# project1.net
KiCad netlist of a schematic drawn in Altium Designer
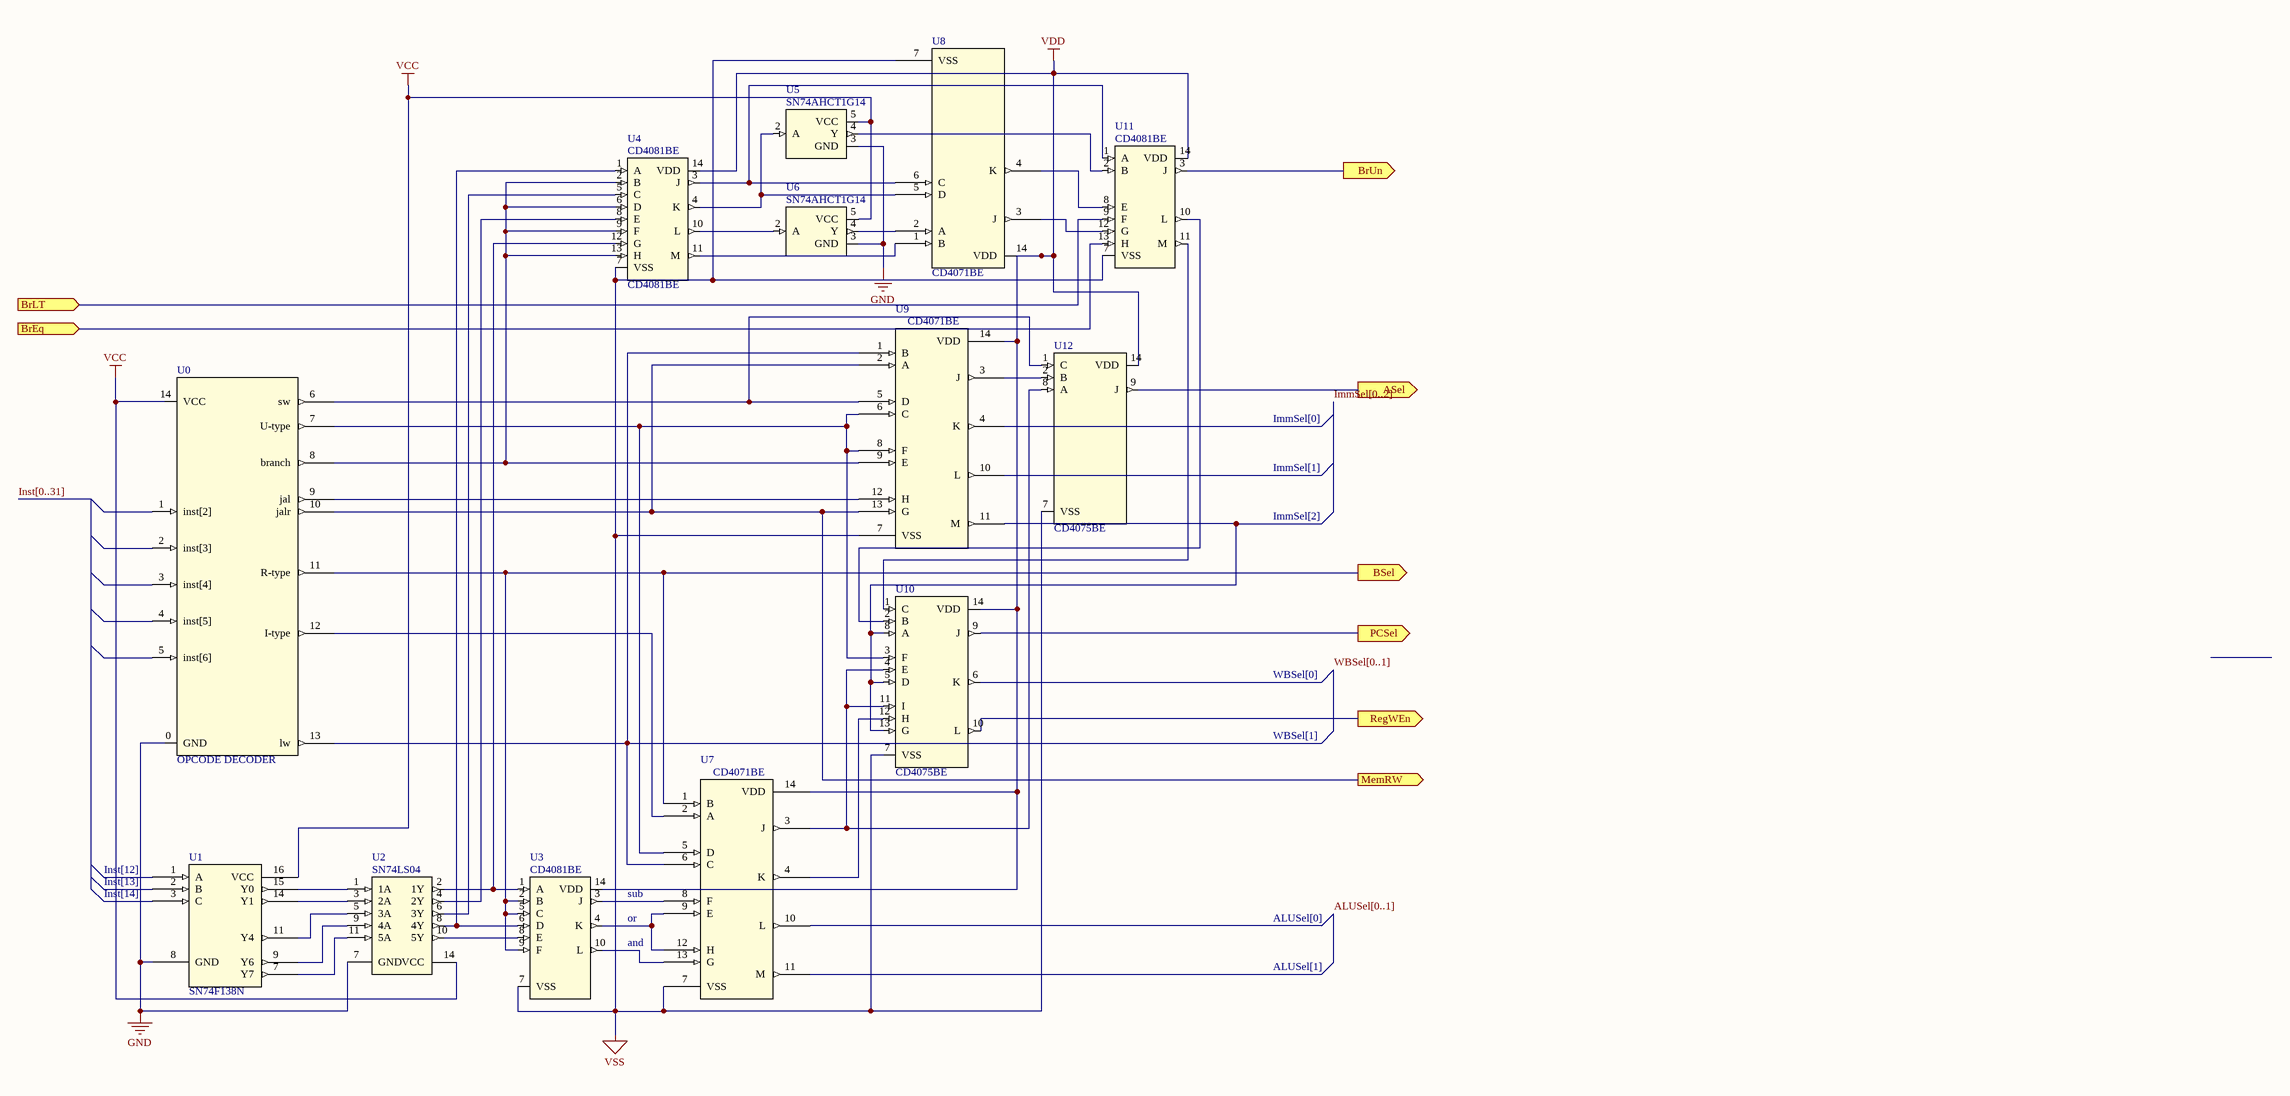
[diagram p0: project1.SchDoc]

(export (version "E")
  (design (tool "Eeschema 10.0.6"))
  (components
    (comp (ref "U0") (value "OPCODE DECODER") (libsource (lib "Project1") (part "OPCODE DECODER FS")))
    (comp (ref "U1")
      (value "SN74F138N")
      (footprint "N16")
      (description "No Description Available")
      (fields (field (name "COPYRIGHT") "Copyright (C) 2023 Ultra Librarian. All rights reserved."))
      (libsource (lib "SN74F138N") (part "SN74F138N_1"))
    )
    (comp (ref "U2")
      (value "SN74LS04N")
      (footprint "N14")
      (description "No Description Available")
      (fields (field (name "COPYRIGHT") "Copyright (C) 2023 Ultra Librarian. All rights reserved."))
      (libsource (lib "SN74LS04N") (part "SN74LS04N"))
    )
    (comp (ref "U3")
      (value "CD4081BE")
      (footprint "N14")
      (description "No Description Available")
      (fields (field (name "COPYRIGHT") "Copyright (C) 2023 Ultra Librarian. All rights reserved."))
      (libsource (lib "CD4081BE") (part "CD4081BE"))
    )
    (comp (ref "U4")
      (value "CD4081BE")
      (footprint "N14")
      (description "No Description Available")
      (fields (field (name "COPYRIGHT") "Copyright (C) 2023 Ultra Librarian. All rights reserved."))
      (libsource (lib "CD4081BE") (part "CD4081BE"))
    )
    (comp (ref "U5")
      (value "CAHCT1G14QDCKRQ1")
      (footprint "DCK5_TEX")
      (description "No Description Available")
      (fields (field (name "COPYRIGHT") "Copyright (C) 2023 Ultra Librarian. All rights reserved."))
      (libsource (lib "CAHCT1G14QDCKRQ1") (part "CAHCT1G14QDCKRQ1"))
    )
    (comp (ref "U6")
      (value "AHCT1G14QDCKRQ1")
      (footprint "DCK5_TEX")
      (description "No Description Available")
      (fields
        (field (name "MANUFACTURER_PART_NUMBER") "CAHCT1G14QDCKRQ1")
        (field (name "COPYRIGHT") "Copyright (C) 2023 Ultra Librarian. All rights reserved.")
      )
      (libsource (lib "CAHCT1G14QDCKRQ1") (part "CAHCT1G14QDCKRQ1"))
    )
    (comp (ref "U7")
      (value "CD4071BE")
      (footprint "N14")
      (description "No Description Available")
      (fields (field (name "COPYRIGHT") "Copyright (C) 2023 Ultra Librarian. All rights reserved."))
      (libsource (lib "") (part "CD4071BE_1"))
    )
    (comp (ref "U8")
      (value "CD4071BE")
      (footprint "N14")
      (description "No Description Available")
      (fields (field (name "COPYRIGHT") "Copyright (C) 2023 Ultra Librarian. All rights reserved."))
      (libsource (lib "CD4071BE") (part "CD4071BE"))
    )
    (comp (ref "U9")
      (value "CD4071BE")
      (footprint "N14")
      (description "No Description Available")
      (fields (field (name "COPYRIGHT") "Copyright (C) 2023 Ultra Librarian. All rights reserved."))
      (libsource (lib "") (part "CD4071BE_1"))
    )
    (comp (ref "U10")
      (value "CD4075BE")
      (footprint "N14")
      (description "No Description Available")
      (fields (field (name "COPYRIGHT") "Copyright (C) 2023 Ultra Librarian. All rights reserved."))
      (libsource (lib "CD4075BE") (part "CD4075BE"))
    )
    (comp (ref "U11")
      (value "CD4081BE")
      (footprint "N14")
      (description "No Description Available")
      (fields (field (name "COPYRIGHT") "Copyright (C) 2023 Ultra Librarian. All rights reserved."))
      (libsource (lib "CD4081BE") (part "CD4081BE"))
    )
    (comp (ref "U12")
      (value "CD4075BE")
      (footprint "N14")
      (description "No Description Available")
      (fields (field (name "COPYRIGHT") "Copyright (C) 2023 Ultra Librarian. All rights reserved."))
      (libsource (lib "CD4075BE") (part "CD4075BE"))
    )
  )
  (nets
    (net (code "41") (name "/ASel") (class "Default")
      (node (ref "U12") (pin "9") (pinfunction "J_9") (pintype "output"))
    )
    (net (code "42") (name "/BSel") (class "Default")
      (node (ref "U0") (pin "11") (pinfunction "R-type_11") (pintype "output"))
      (node (ref "U3") (pin "2") (pinfunction "B_2") (pintype "input"))
      (node (ref "U3") (pin "5") (pinfunction "C_5") (pintype "input"))
      (node (ref "U3") (pin "9") (pinfunction "F_9") (pintype "input"))
      (node (ref "U7") (pin "1") (pinfunction "B_1") (pintype "input"))
    )
    (net (code "43") (name "/BrEq") (class "Default")
      (node (ref "U11") (pin "13") (pinfunction "H_13") (pintype "input"))
    )
    (net (code "44") (name "/BrLT") (class "Default")
      (node (ref "U11") (pin "9") (pinfunction "F_9") (pintype "input"))
    )
    (net (code "45") (name "/BrUn") (class "Default")
      (node (ref "U11") (pin "3") (pinfunction "J_3") (pintype "output"))
    )
    (net (code "48") (name "/MemRW") (class "Default")
      (node (ref "U0") (pin "10") (pinfunction "jalr_10") (pintype "output"))
      (node (ref "U9") (pin "13") (pinfunction "G_13") (pintype "input"))
      (node (ref "U9") (pin "2") (pinfunction "A_2") (pintype "input"))
    )
    (net (code "49") (name "/PCSel") (class "Default")
      (node (ref "U10") (pin "9") (pinfunction "J_9") (pintype "output"))
    )
    (net (code "50") (name "/RegWEn") (class "Default")
      (node (ref "U10") (pin "10") (pinfunction "L_10") (pintype "output"))
    )
    (net (code "52") (name "GND") (class "Default")
      (node (ref "U0") (pin "0") (pinfunction "GND_0") (pintype "power_in"))
      (node (ref "U1") (pin "8") (pinfunction "GND_8") (pintype "power_in"))
      (node (ref "U2") (pin "7") (pinfunction "GND_7") (pintype "power_in"))
      (node (ref "U5") (pin "3") (pinfunction "GND_3") (pintype "power_in"))
      (node (ref "U6") (pin "3") (pinfunction "GND_3") (pintype "power_in"))
    )
    (net (code "53") (name "Net-(U0-I-type)") (class "Default")
      (node (ref "U0") (pin "12") (pinfunction "I-type_12") (pintype "output"))
      (node (ref "U7") (pin "2") (pinfunction "A_2") (pintype "input"))
    )
    (net (code "54") (name "Net-(U0-U-type)") (class "Default")
      (node (ref "U0") (pin "7") (pinfunction "U-type_7") (pintype "output"))
      (node (ref "U10") (pin "3") (pinfunction "F_3") (pintype "input"))
      (node (ref "U7") (pin "5") (pinfunction "D_5") (pintype "input"))
      (node (ref "U9") (pin "6") (pinfunction "C_6") (pintype "input"))
      (node (ref "U9") (pin "8") (pinfunction "F_8") (pintype "input"))
    )
    (net (code "55") (name "Net-(U0-branch)") (class "Default")
      (node (ref "U0") (pin "8") (pinfunction "branch_8") (pintype "output"))
      (node (ref "U4") (pin "13") (pinfunction "H_13") (pintype "input"))
      (node (ref "U4") (pin "2") (pinfunction "B_2") (pintype "input"))
      (node (ref "U4") (pin "6") (pinfunction "D_6") (pintype "input"))
      (node (ref "U4") (pin "9") (pinfunction "F_9") (pintype "input"))
      (node (ref "U9") (pin "9") (pinfunction "E_9") (pintype "input"))
    )
    (net (code "56") (name "Net-(U0-jal)") (class "Default")
      (node (ref "U0") (pin "9") (pinfunction "jal_9") (pintype "output"))
      (node (ref "U9") (pin "12") (pinfunction "H_12") (pintype "input"))
    )
    (net (code "57") (name "Net-(U0-lw)") (class "Default")
      (node (ref "U0") (pin "13") (pinfunction "lw_13") (pintype "output"))
      (node (ref "U7") (pin "6") (pinfunction "C_6") (pintype "input"))
      (node (ref "U9") (pin "1") (pinfunction "B_1") (pintype "input"))
    )
    (net (code "58") (name "Net-(U0-sw)") (class "Default")
      (node (ref "U0") (pin "6") (pinfunction "sw_6") (pintype "output"))
      (node (ref "U12") (pin "1") (pinfunction "C_1") (pintype "input"))
      (node (ref "U9") (pin "5") (pinfunction "D_5") (pintype "input"))
    )
    (net (code "59") (name "Net-(U1-Y0)") (class "Default")
      (node (ref "U1") (pin "15") (pinfunction "Y0_15") (pintype "output"))
      (node (ref "U2") (pin "1") (pinfunction "1A_1") (pintype "input"))
    )
    (net (code "60") (name "Net-(U1-Y1)") (class "Default")
      (node (ref "U1") (pin "14") (pinfunction "Y1_14") (pintype "output"))
      (node (ref "U2") (pin "3") (pinfunction "2A_3") (pintype "input"))
    )
    (net (code "61") (name "Net-(U1-Y4)") (class "Default")
      (node (ref "U1") (pin "11") (pinfunction "Y4_11") (pintype "output"))
      (node (ref "U2") (pin "5") (pinfunction "3A_5") (pintype "input"))
    )
    (net (code "62") (name "Net-(U1-Y6)") (class "Default")
      (node (ref "U1") (pin "9") (pinfunction "Y6_9") (pintype "output"))
      (node (ref "U2") (pin "9") (pinfunction "4A_9") (pintype "input"))
    )
    (net (code "63") (name "Net-(U1-Y7)") (class "Default")
      (node (ref "U1") (pin "7") (pinfunction "Y7_7") (pintype "output"))
      (node (ref "U2") (pin "11") (pinfunction "5A_11") (pintype "input"))
    )
    (net (code "64") (name "Net-(U2-1Y)") (class "Default")
      (node (ref "U2") (pin "2") (pinfunction "1Y_2") (pintype "output"))
      (node (ref "U3") (pin "1") (pinfunction "A_1") (pintype "input"))
      (node (ref "U4") (pin "12") (pinfunction "G_12") (pintype "input"))
    )
    (net (code "65") (name "Net-(U2-2Y)") (class "Default")
      (node (ref "U2") (pin "4") (pinfunction "2Y_4") (pintype "output"))
      (node (ref "U4") (pin "8") (pinfunction "E_8") (pintype "input"))
    )
    (net (code "66") (name "Net-(U2-3Y)") (class "Default")
      (node (ref "U2") (pin "6") (pinfunction "3Y_6") (pintype "output"))
      (node (ref "U4") (pin "5") (pinfunction "C_5") (pintype "input"))
    )
    (net (code "67") (name "Net-(U2-4Y)") (class "Default")
      (node (ref "U2") (pin "8") (pinfunction "4Y_8") (pintype "output"))
      (node (ref "U3") (pin "6") (pinfunction "D_6") (pintype "input"))
      (node (ref "U4") (pin "1") (pinfunction "A_1") (pintype "input"))
    )
    (net (code "68") (name "Net-(U2-5Y)") (class "Default")
      (node (ref "U2") (pin "10") (pinfunction "5Y_10") (pintype "output"))
      (node (ref "U3") (pin "8") (pinfunction "E_8") (pintype "input"))
    )
    (net (code "69") (name "Net-(U3-J)") (class "Default")
      (node (ref "U3") (pin "3") (pinfunction "J_3") (pintype "output"))
      (node (ref "U7") (pin "8") (pinfunction "F_8") (pintype "input"))
    )
    (net (code "70") (name "Net-(U3-K)") (class "Default")
      (node (ref "U3") (pin "4") (pinfunction "K_4") (pintype "output"))
      (node (ref "U7") (pin "12") (pinfunction "H_12") (pintype "input"))
      (node (ref "U7") (pin "9") (pinfunction "E_9") (pintype "input"))
    )
    (net (code "71") (name "Net-(U3-L)") (class "Default")
      (node (ref "U3") (pin "10") (pinfunction "L_10") (pintype "output"))
      (node (ref "U7") (pin "13") (pinfunction "G_13") (pintype "input"))
    )
    (net (code "72") (name "Net-(U4-K)") (class "Default")
      (node (ref "U4") (pin "4") (pinfunction "K_4") (pintype "output"))
      (node (ref "U5") (pin "2") (pinfunction "A_2") (pintype "input"))
      (node (ref "U8") (pin "5") (pinfunction "D_5") (pintype "input"))
    )
    (net (code "73") (name "Net-(U4-L)") (class "Default")
      (node (ref "U4") (pin "10") (pinfunction "L_10") (pintype "output"))
      (node (ref "U6") (pin "2") (pinfunction "A_2") (pintype "input"))
    )
    (net (code "74") (name "Net-(U4-M)") (class "Default")
      (node (ref "U4") (pin "11") (pinfunction "M_11") (pintype "output"))
      (node (ref "U8") (pin "1") (pinfunction "B_1") (pintype "input"))
    )
    (net (code "75") (name "Net-(U6-Y)") (class "Default")
      (node (ref "U6") (pin "4") (pinfunction "Y_4") (pintype "output"))
      (node (ref "U8") (pin "2") (pinfunction "A_2") (pintype "input"))
    )
    (net (code "76") (name "Net-(U10-A)") (class "Default")
      (node (ref "U10") (pin "13") (pinfunction "G_13") (pintype "input"))
      (node (ref "U10") (pin "5") (pinfunction "D_5") (pintype "input"))
      (node (ref "U10") (pin "8") (pinfunction "A_8") (pintype "input"))
      (node (ref "U9") (pin "11") (pinfunction "M_11") (pintype "output"))
    )
    (net (code "77") (name "Net-(U10-B)") (class "Default")
      (node (ref "U10") (pin "2") (pinfunction "B_2") (pintype "input"))
      (node (ref "U11") (pin "10") (pinfunction "L_10") (pintype "output"))
    )
    (net (code "78") (name "Net-(U10-C)") (class "Default")
      (node (ref "U10") (pin "1") (pinfunction "C_1") (pintype "input"))
      (node (ref "U11") (pin "11") (pinfunction "M_11") (pintype "output"))
    )
    (net (code "79") (name "Net-(U10-E)") (class "Default")
      (node (ref "U10") (pin "11") (pinfunction "I_11") (pintype "input"))
      (node (ref "U10") (pin "4") (pinfunction "E_4") (pintype "input"))
      (node (ref "U12") (pin "8") (pinfunction "A_8") (pintype "input"))
      (node (ref "U7") (pin "3") (pinfunction "J_3") (pintype "output"))
    )
    (net (code "80") (name "Net-(U10-H)") (class "Default")
      (node (ref "U10") (pin "12") (pinfunction "H_12") (pintype "input"))
      (node (ref "U7") (pin "4") (pinfunction "K_4") (pintype "output"))
    )
    (net (code "81") (name "Net-(U11-A)") (class "Default")
      (node (ref "U11") (pin "1") (pinfunction "A_1") (pintype "input"))
      (node (ref "U4") (pin "3") (pinfunction "J_3") (pintype "output"))
      (node (ref "U8") (pin "6") (pinfunction "C_6") (pintype "input"))
    )
    (net (code "82") (name "Net-(U11-B)") (class "Default")
      (node (ref "U11") (pin "2") (pinfunction "B_2") (pintype "input"))
      (node (ref "U5") (pin "4") (pinfunction "Y_4") (pintype "output"))
    )
    (net (code "83") (name "Net-(U11-E)") (class "Default")
      (node (ref "U11") (pin "8") (pinfunction "E_8") (pintype "input"))
      (node (ref "U8") (pin "4") (pinfunction "K_4") (pintype "output"))
    )
    (net (code "84") (name "Net-(U11-G)") (class "Default")
      (node (ref "U11") (pin "12") (pinfunction "G_12") (pintype "input"))
      (node (ref "U8") (pin "3") (pinfunction "J_3") (pintype "output"))
    )
    (net (code "85") (name "Net-(U12-B)") (class "Default")
      (node (ref "U12") (pin "2") (pinfunction "B_2") (pintype "input"))
      (node (ref "U9") (pin "3") (pinfunction "J_3") (pintype "output"))
    )
    (net (code "86") (name "VCC") (class "Default")
      (node (ref "U0") (pin "14") (pinfunction "VCC_14") (pintype "power_in"))
      (node (ref "U1") (pin "16") (pinfunction "VCC_16") (pintype "power_in"))
      (node (ref "U2") (pin "14") (pinfunction "VCC_14") (pintype "power_in"))
      (node (ref "U5") (pin "5") (pinfunction "VCC_5") (pintype "power_in"))
      (node (ref "U6") (pin "5") (pinfunction "VCC_5") (pintype "power_in"))
    )
    (net (code "87") (name "VDD") (class "Default")
      (node (ref "U10") (pin "14") (pinfunction "VDD_14") (pintype "power_in"))
      (node (ref "U11") (pin "14") (pinfunction "VDD_14") (pintype "power_in"))
      (node (ref "U12") (pin "14") (pinfunction "VDD_14") (pintype "power_in"))
      (node (ref "U3") (pin "14") (pinfunction "VDD_14") (pintype "power_in"))
      (node (ref "U4") (pin "14") (pinfunction "VDD_14") (pintype "power_in"))
      (node (ref "U7") (pin "14") (pinfunction "VDD_14") (pintype "power_in"))
      (node (ref "U8") (pin "14") (pinfunction "VDD_14") (pintype "power_in"))
      (node (ref "U9") (pin "14") (pinfunction "VDD_14") (pintype "power_in"))
    )
    (net (code "88") (name "VSS") (class "Default")
      (node (ref "U10") (pin "7") (pinfunction "VSS_7") (pintype "power_in"))
      (node (ref "U11") (pin "7") (pinfunction "VSS_7") (pintype "power_in"))
      (node (ref "U12") (pin "7") (pinfunction "VSS_7") (pintype "power_in"))
      (node (ref "U3") (pin "7") (pinfunction "VSS_7") (pintype "power_in"))
      (node (ref "U4") (pin "7") (pinfunction "VSS_7") (pintype "power_in"))
      (node (ref "U7") (pin "7") (pinfunction "VSS_7") (pintype "power_in"))
      (node (ref "U8") (pin "7") (pinfunction "VSS_7") (pintype "power_in"))
      (node (ref "U9") (pin "7") (pinfunction "VSS_7") (pintype "power_in"))
    )
    (net (code "89") (name "unconnected-(U0-inst[2]-Pad1)") (class "Default")
      (node (ref "U0") (pin "1") (pinfunction "inst[2]_1") (pintype "input"))
    )
    (net (code "90") (name "unconnected-(U0-inst[3]-Pad2)") (class "Default")
      (node (ref "U0") (pin "2") (pinfunction "inst[3]_2") (pintype "input"))
    )
    (net (code "91") (name "unconnected-(U0-inst[4]-Pad3)") (class "Default")
      (node (ref "U0") (pin "3") (pinfunction "inst[4]_3") (pintype "input"))
    )
    (net (code "92") (name "unconnected-(U0-inst[5]-Pad4)") (class "Default")
      (node (ref "U0") (pin "4") (pinfunction "inst[5]_4") (pintype "input"))
    )
    (net (code "93") (name "unconnected-(U0-inst[6]-Pad5)") (class "Default")
      (node (ref "U0") (pin "5") (pinfunction "inst[6]_5") (pintype "input"))
    )
    (net (code "94") (name "unconnected-(U1-A-Pad1)") (class "Default")
      (node (ref "U1") (pin "1") (pinfunction "A_1") (pintype "input"))
    )
    (net (code "95") (name "unconnected-(U1-B-Pad2)") (class "Default")
      (node (ref "U1") (pin "2") (pinfunction "B_2") (pintype "input"))
    )
    (net (code "96") (name "unconnected-(U1-C-Pad3)") (class "Default")
      (node (ref "U1") (pin "3") (pinfunction "C_3") (pintype "input"))
    )
    (net (code "97") (name "unconnected-(U1-Y2-Pad13)") (class "Default")
      (node (ref "U1") (pin "13") (pinfunction "Y2_13") (pintype "output"))
    )
    (net (code "98") (name "unconnected-(U1-Y3-Pad12)") (class "Default")
      (node (ref "U1") (pin "12") (pinfunction "Y3_12") (pintype "output"))
    )
    (net (code "99") (name "unconnected-(U1-Y5-Pad10)") (class "Default")
      (node (ref "U1") (pin "10") (pinfunction "Y5_10") (pintype "output"))
    )
    (net (code "100") (name "unconnected-(U2-6A-Pad13)") (class "Default")
      (node (ref "U2") (pin "13") (pinfunction "6A_13") (pintype "input"))
    )
    (net (code "101") (name "unconnected-(U2-6Y-Pad12)") (class "Default")
      (node (ref "U2") (pin "12") (pinfunction "6Y_12") (pintype "output"))
    )
    (net (code "102") (name "unconnected-(U3-G-Pad12)") (class "Default")
      (node (ref "U3") (pin "12") (pinfunction "G_12") (pintype "input"))
    )
    (net (code "103") (name "unconnected-(U3-H-Pad13)") (class "Default")
      (node (ref "U3") (pin "13") (pinfunction "H_13") (pintype "input"))
    )
    (net (code "104") (name "unconnected-(U3-M-Pad11)") (class "Default")
      (node (ref "U3") (pin "11") (pinfunction "M_11") (pintype "output"))
    )
    (net (code "105") (name "unconnected-(U7-L-Pad10)") (class "Default")
      (node (ref "U7") (pin "10") (pinfunction "L_10") (pintype "output"))
    )
    (net (code "106") (name "unconnected-(U7-M-Pad11)") (class "Default")
      (node (ref "U7") (pin "11") (pinfunction "M_11") (pintype "output"))
    )
    (net (code "107") (name "unconnected-(U8-E-Pad9)") (class "Default")
      (node (ref "U8") (pin "9") (pinfunction "E_9") (pintype "input"))
    )
    (net (code "108") (name "unconnected-(U8-F-Pad8)") (class "Default")
      (node (ref "U8") (pin "8") (pinfunction "F_8") (pintype "input"))
    )
    (net (code "109") (name "unconnected-(U8-G-Pad13)") (class "Default")
      (node (ref "U8") (pin "13") (pinfunction "G_13") (pintype "input"))
    )
    (net (code "110") (name "unconnected-(U8-H-Pad12)") (class "Default")
      (node (ref "U8") (pin "12") (pinfunction "H_12") (pintype "input"))
    )
    (net (code "111") (name "unconnected-(U8-L-Pad10)") (class "Default")
      (node (ref "U8") (pin "10") (pinfunction "L_10") (pintype "output"))
    )
    (net (code "112") (name "unconnected-(U8-M-Pad11)") (class "Default")
      (node (ref "U8") (pin "11") (pinfunction "M_11") (pintype "output"))
    )
    (net (code "113") (name "unconnected-(U9-K-Pad4)") (class "Default")
      (node (ref "U9") (pin "4") (pinfunction "K_4") (pintype "output"))
    )
    (net (code "114") (name "unconnected-(U9-L-Pad10)") (class "Default")
      (node (ref "U9") (pin "10") (pinfunction "L_10") (pintype "output"))
    )
    (net (code "115") (name "unconnected-(U10-K-Pad6)") (class "Default")
      (node (ref "U10") (pin "6") (pinfunction "K_6") (pintype "output"))
    )
    (net (code "116") (name "unconnected-(U11-C-Pad5)") (class "Default")
      (node (ref "U11") (pin "5") (pinfunction "C_5") (pintype "input"))
    )
    (net (code "117") (name "unconnected-(U11-D-Pad6)") (class "Default")
      (node (ref "U11") (pin "6") (pinfunction "D_6") (pintype "input"))
    )
    (net (code "118") (name "unconnected-(U11-K-Pad4)") (class "Default")
      (node (ref "U11") (pin "4") (pinfunction "K_4") (pintype "output"))
    )
    (net (code "119") (name "unconnected-(U12-D-Pad5)") (class "Default")
      (node (ref "U12") (pin "5") (pinfunction "D_5") (pintype "input"))
    )
    (net (code "120") (name "unconnected-(U12-E-Pad4)") (class "Default")
      (node (ref "U12") (pin "4") (pinfunction "E_4") (pintype "input"))
    )
    (net (code "121") (name "unconnected-(U12-F-Pad3)") (class "Default")
      (node (ref "U12") (pin "3") (pinfunction "F_3") (pintype "input"))
    )
    (net (code "122") (name "unconnected-(U12-G-Pad13)") (class "Default")
      (node (ref "U12") (pin "13") (pinfunction "G_13") (pintype "input"))
    )
    (net (code "123") (name "unconnected-(U12-H-Pad12)") (class "Default")
      (node (ref "U12") (pin "12") (pinfunction "H_12") (pintype "input"))
    )
    (net (code "124") (name "unconnected-(U12-I-Pad11)") (class "Default")
      (node (ref "U12") (pin "11") (pinfunction "I_11") (pintype "input"))
    )
    (net (code "125") (name "unconnected-(U12-K-Pad6)") (class "Default")
      (node (ref "U12") (pin "6") (pinfunction "K_6") (pintype "output"))
    )
    (net (code "126") (name "unconnected-(U12-L-Pad10)") (class "Default")
      (node (ref "U12") (pin "10") (pinfunction "L_10") (pintype "output"))
    )
  )
)
